# SparkFun_Lipo_Fuel_Gauge.net
KiCad netlist of a schematic drawn in EAGLE
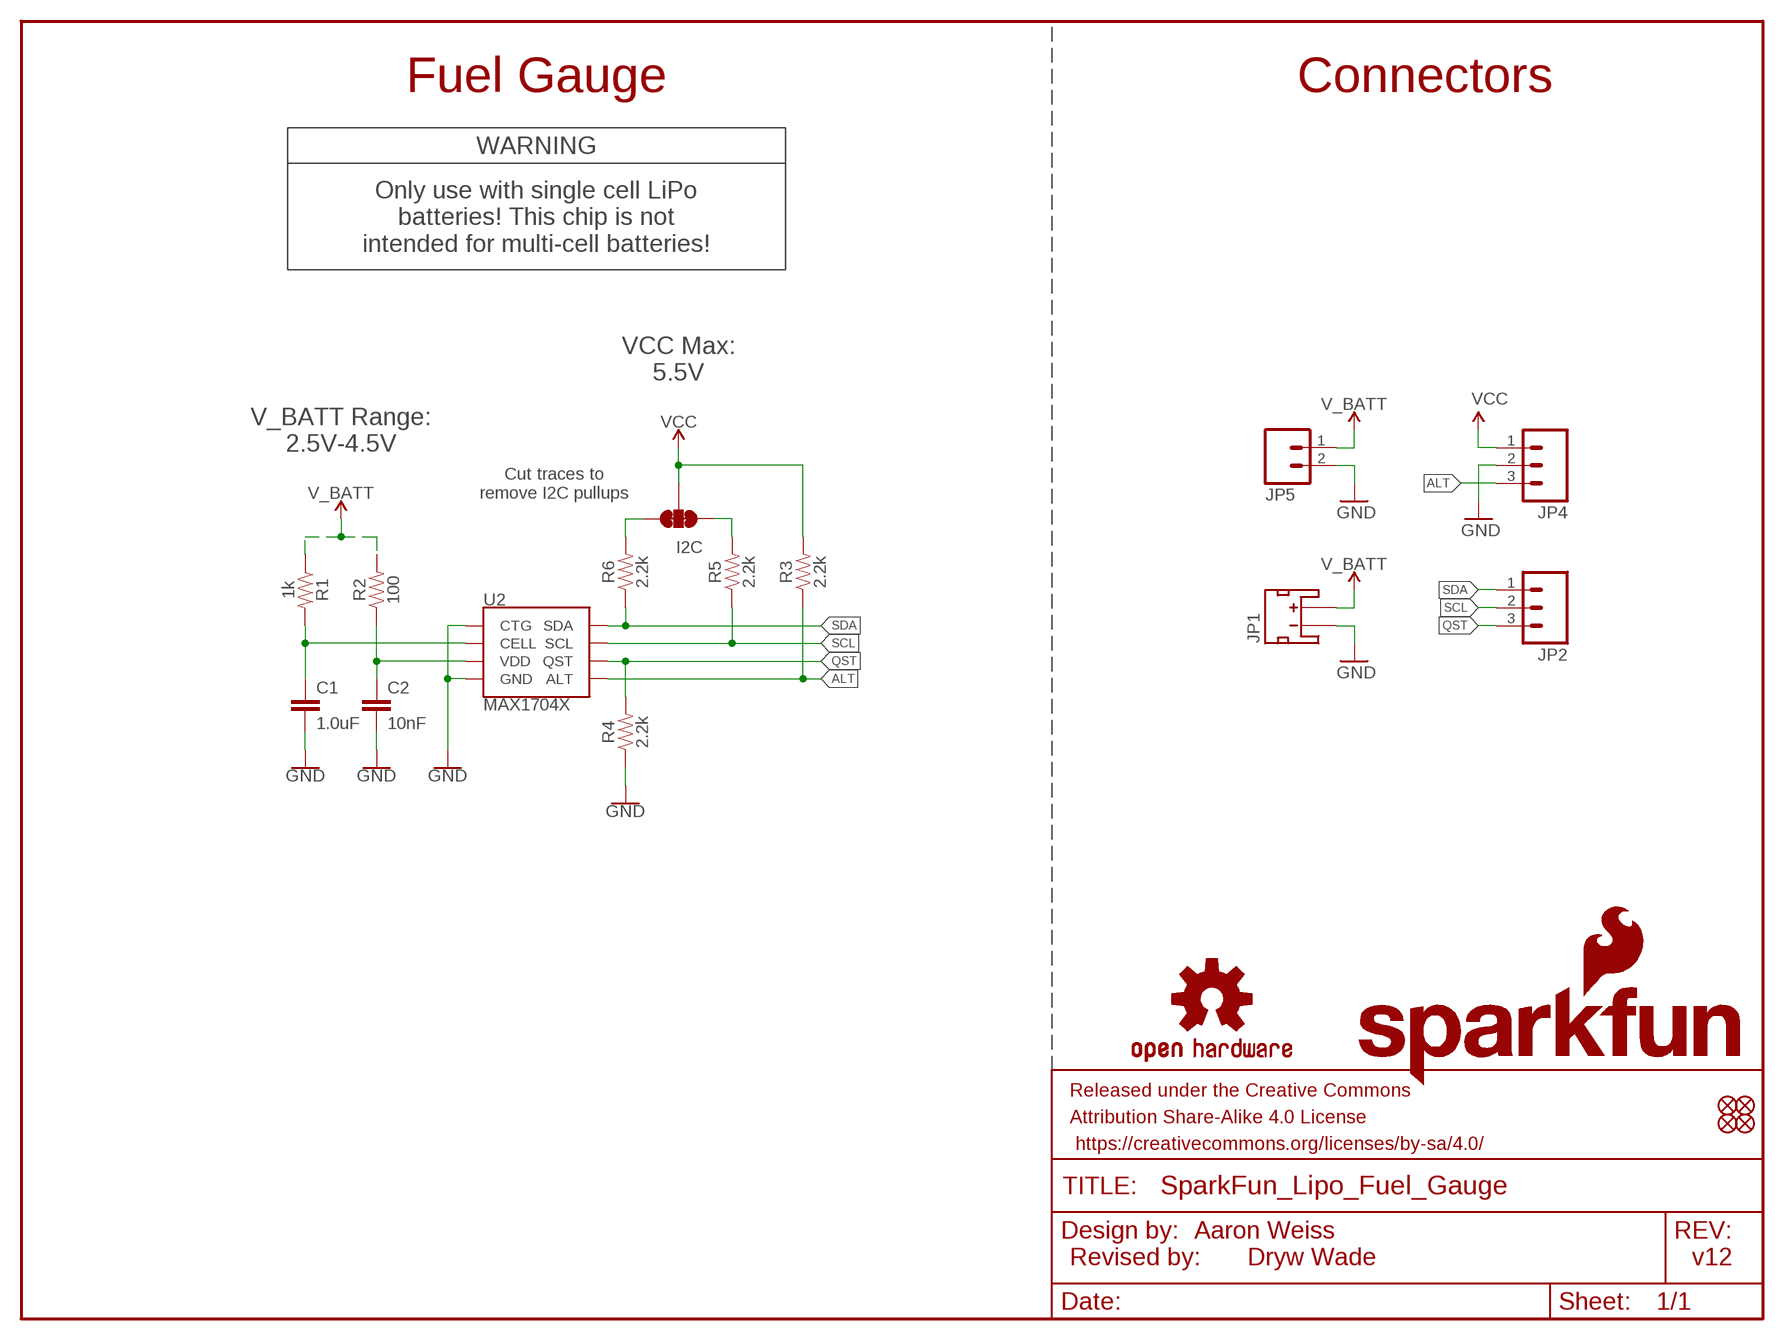
[diagram p0: schematic, sheet 1]

(export (version "E")
  (design (tool "Eeschema 10.0.6"))
  (components
    (comp (ref "C1")
      (value "1.0uF")
      (footprint "eagle-import:0402-TIGHT")
      (libsource (lib "eagle-import") (part "1.0UF-0402T-16V-10%"))
    )
    (comp (ref "C2")
      (value "10nF")
      (footprint "eagle-import:0402-TIGHT")
      (libsource (lib "eagle-import") (part "10NF-0402T-25V-10%"))
    )
    (comp (ref "FRAME1")
      (value "FRAME-LETTER")
      (footprint "eagle-import:CREATIVE_COMMONS")
      (libsource (lib "eagle-import") (part "FRAME-LETTER"))
    )
    (comp (ref "I2C")
      (value "JUMPER-SMT_3_2-NC_TRACE_SILK")
      (footprint "eagle-import:SMT-JUMPER_3_2-NC_TRACE_SILK")
      (libsource (lib "eagle-import") (part "JUMPER-SMT_3_2-NC_TRACE_SILK"))
    )
    (comp (ref "JP1")
      (value "input")
      (footprint "eagle-import:JST-2-SMD")
      (libsource (lib "eagle-import") (part "JST_2MM_MALE"))
    )
    (comp (ref "JP2")
      (value "CONN_031X03_NO_SILK")
      (footprint "eagle-import:1X03_NO_SILK")
      (libsource (lib "eagle-import") (part "CONN_031X03_NO_SILK"))
    )
    (comp (ref "JP3")
      (value "SFE_LOGO_FLAME.1_INCH")
      (footprint "eagle-import:SFE_LOGO_FLAME_.1")
      (libsource (lib "eagle-import") (part "SFE_LOGO_FLAME.1_INCH"))
    )
    (comp (ref "JP4")
      (value "CONN_031X03_NO_SILK")
      (footprint "eagle-import:1X03_NO_SILK")
      (libsource (lib "eagle-import") (part "CONN_031X03_NO_SILK"))
    )
    (comp (ref "JP5")
      (value "CONN_021X02_NO_SILK")
      (footprint "eagle-import:1X02_NO_SILK")
      (libsource (lib "eagle-import") (part "CONN_021X02_NO_SILK"))
    )
    (comp (ref "JP6")
      (value "FIDUCIALUFIDUCIAL")
      (footprint "eagle-import:FIDUCIAL-MICRO")
      (libsource (lib "eagle-import") (part "FIDUCIALUFIDUCIAL"))
    )
    (comp (ref "JP7")
      (value "FIDUCIALUFIDUCIAL")
      (footprint "eagle-import:FIDUCIAL-MICRO")
      (libsource (lib "eagle-import") (part "FIDUCIALUFIDUCIAL"))
    )
    (comp (ref "JP8")
      (value "FIDUCIALUFIDUCIAL")
      (footprint "eagle-import:FIDUCIAL-MICRO")
      (libsource (lib "eagle-import") (part "FIDUCIALUFIDUCIAL"))
    )
    (comp (ref "JP9")
      (value "FIDUCIALUFIDUCIAL")
      (footprint "eagle-import:FIDUCIAL-MICRO")
      (libsource (lib "eagle-import") (part "FIDUCIALUFIDUCIAL"))
    )
    (comp (ref "LOGO1")
      (value "SFE_LOGO_NAME_FLAMEBLANK")
      (footprint "eagle-import:BLANK")
      (libsource (lib "eagle-import") (part "SFE_LOGO_NAME_FLAMEBLANK"))
    )
    (comp (ref "R1")
      (value "1k")
      (footprint "eagle-import:0402-TIGHT")
      (libsource (lib "eagle-import") (part "1KOHM-0402T-1/16W-1%"))
    )
    (comp (ref "R2")
      (value "100")
      (footprint "eagle-import:0402-TIGHT")
      (libsource (lib "eagle-import") (part "100OHM-0402-TIGHT-1/16W-1%"))
    )
    (comp (ref "R3")
      (value "2.2k")
      (footprint "eagle-import:0402-TIGHT")
      (libsource (lib "eagle-import") (part "2.2KOHM-0402T-1/16W-1%"))
    )
    (comp (ref "R4")
      (value "2.2k")
      (footprint "eagle-import:0402-TIGHT")
      (libsource (lib "eagle-import") (part "2.2KOHM-0402T-1/16W-1%"))
    )
    (comp (ref "R5")
      (value "2.2k")
      (footprint "eagle-import:0402-TIGHT")
      (libsource (lib "eagle-import") (part "2.2KOHM-0402T-1/16W-1%"))
    )
    (comp (ref "R6")
      (value "2.2k")
      (footprint "eagle-import:0402-TIGHT")
      (libsource (lib "eagle-import") (part "2.2KOHM-0402T-1/16W-1%"))
    )
    (comp (ref "U$1")
      (value "OSHW-LOGOS")
      (footprint "eagle-import:OSHW-LOGO-S")
      (libsource (lib "eagle-import") (part "OSHW-LOGOS"))
    )
    (comp (ref "U2")
      (value "MAX1704X")
      (footprint "eagle-import:TDFN-8")
      (libsource (lib "eagle-import") (part "MAX1704X"))
    )
  )
  (nets
    (net (code "1") (name "ALT") (class "Default")
      (node (ref "JP4") (pin "3") (pinfunction "3_3") (pintype "passive"))
      (node (ref "R3") (pin "1") (pinfunction "1_1") (pintype "passive"))
      (node (ref "U2") (pin "5") (pinfunction "ALT_5") (pintype "bidirectional"))
    )
    (net (code "2") (name "GND") (class "Default")
      (node (ref "C1") (pin "2") (pinfunction "2_2") (pintype "passive"))
      (node (ref "C2") (pin "2") (pinfunction "2_2") (pintype "passive"))
      (node (ref "JP1") (pin "1") (pinfunction "-_1") (pintype "bidirectional"))
      (node (ref "JP4") (pin "2") (pinfunction "2_2") (pintype "passive"))
      (node (ref "JP5") (pin "2") (pinfunction "2_2") (pintype "passive"))
      (node (ref "R4") (pin "1") (pinfunction "1_1") (pintype "passive"))
      (node (ref "U2") (pin "1") (pinfunction "CTG_1") (pintype "bidirectional"))
      (node (ref "U2") (pin "4") (pinfunction "GND_4") (pintype "bidirectional"))
      (node (ref "U2") (pin "EP") (pinfunction "GND_EP") (pintype "bidirectional"))
    )
    (net (code "3") (name "Net-(I2C-Pad1)") (class "Default")
      (node (ref "I2C") (pin "1") (pinfunction "1_1") (pintype "passive"))
      (node (ref "R5") (pin "2") (pinfunction "2_2") (pintype "passive"))
    )
    (net (code "4") (name "Net-(I2C-Pad3)") (class "Default")
      (node (ref "I2C") (pin "3") (pinfunction "3_3") (pintype "passive"))
      (node (ref "R6") (pin "2") (pinfunction "2_2") (pintype "passive"))
    )
    (net (code "5") (name "Net-(U2-CELL)") (class "Default")
      (node (ref "C1") (pin "1") (pinfunction "1_1") (pintype "passive"))
      (node (ref "R1") (pin "2") (pinfunction "2_2") (pintype "passive"))
      (node (ref "U2") (pin "2") (pinfunction "CELL_2") (pintype "bidirectional"))
    )
    (net (code "6") (name "Net-(U2-VDD)") (class "Default")
      (node (ref "C2") (pin "1") (pinfunction "1_1") (pintype "passive"))
      (node (ref "R2") (pin "1") (pinfunction "1_1") (pintype "passive"))
      (node (ref "U2") (pin "3") (pinfunction "VDD_3") (pintype "bidirectional"))
    )
    (net (code "7") (name "QST") (class "Default")
      (node (ref "JP2") (pin "3") (pinfunction "3_3") (pintype "passive"))
      (node (ref "R4") (pin "2") (pinfunction "2_2") (pintype "passive"))
      (node (ref "U2") (pin "6") (pinfunction "QST_6") (pintype "bidirectional"))
    )
    (net (code "8") (name "SCL") (class "Default")
      (node (ref "JP2") (pin "2") (pinfunction "2_2") (pintype "passive"))
      (node (ref "R5") (pin "1") (pinfunction "1_1") (pintype "passive"))
      (node (ref "U2") (pin "7") (pinfunction "SCL_7") (pintype "bidirectional"))
    )
    (net (code "9") (name "SDA") (class "Default")
      (node (ref "JP2") (pin "1") (pinfunction "1_1") (pintype "passive"))
      (node (ref "R6") (pin "1") (pinfunction "1_1") (pintype "passive"))
      (node (ref "U2") (pin "8") (pinfunction "SDA_8") (pintype "bidirectional"))
    )
    (net (code "10") (name "VCC") (class "Default")
      (node (ref "I2C") (pin "2") (pinfunction "2_2") (pintype "passive"))
      (node (ref "JP4") (pin "1") (pinfunction "1_1") (pintype "passive"))
      (node (ref "R3") (pin "2") (pinfunction "2_2") (pintype "passive"))
    )
    (net (code "11") (name "V_BATT") (class "Default")
      (node (ref "JP1") (pin "2") (pinfunction "+_2") (pintype "bidirectional"))
      (node (ref "JP5") (pin "1") (pinfunction "1_1") (pintype "passive"))
      (node (ref "R1") (pin "1") (pinfunction "1_1") (pintype "passive"))
      (node (ref "R2") (pin "2") (pinfunction "2_2") (pintype "passive"))
    )
    (net (code "12") (name "unconnected-(JP1-PAD1-PadNC1)") (class "Default")
      (node (ref "JP1") (pin "NC1") (pinfunction "PAD1_NC1") (pintype "bidirectional"))
    )
    (net (code "13") (name "unconnected-(JP1-PAD2-PadNC2)") (class "Default")
      (node (ref "JP1") (pin "NC2") (pinfunction "PAD2_NC2") (pintype "bidirectional"))
    )
  )
)
